# myRolloCtl_v2.net
KiCad netlist of a schematic drawn in EAGLE
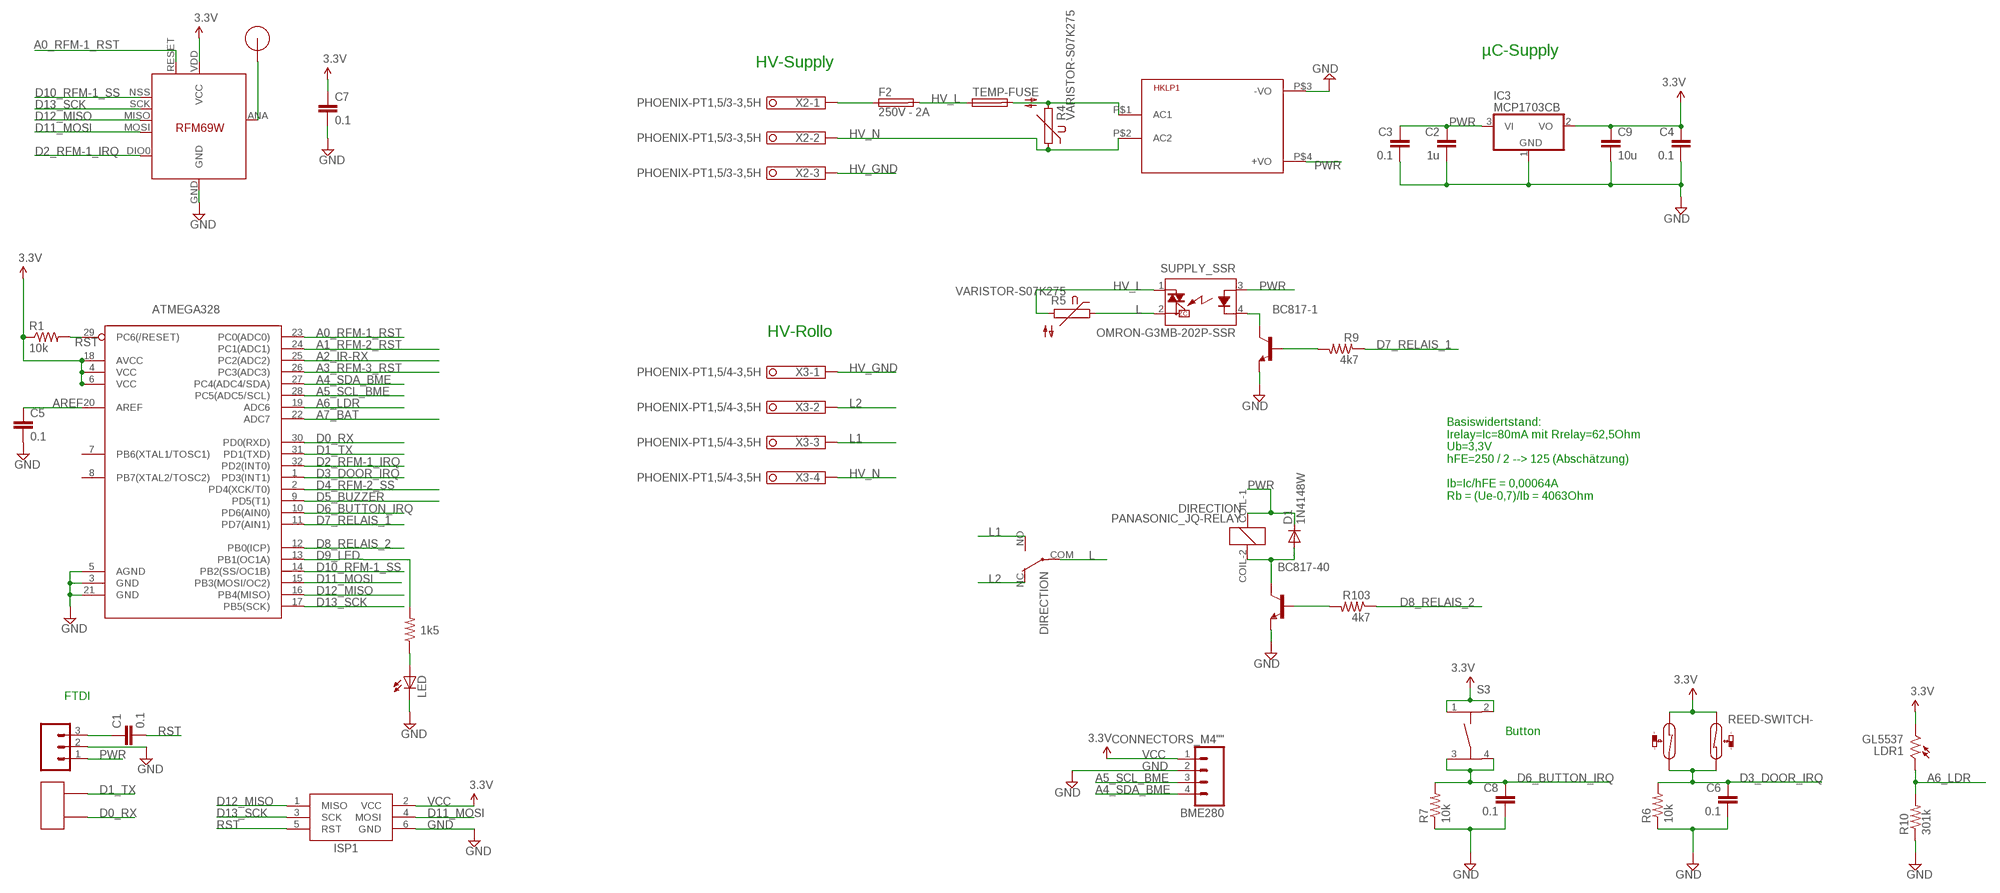
[diagram p0: schematic, sheet 1]

(export (version "E")
  (design (tool "Eeschema 10.0.6"))
  (components
    (comp (ref "ATMEGA328")
      (value "ATMega-328")
      (footprint "eagle-import:TQFP32-08")
      (libsource (lib "eagle-import") (part "ATMEGA168/328TQFP32"))
    )
    (comp (ref "BC817-1")
      (value "BC817-40-NPN-SOT23-BEC")
      (footprint "eagle-import:SOT23-BEC")
      (libsource (lib "eagle-import") (part "-NPN-SOT23-BECBC817-40"))
    )
    (comp (ref "BC817-40")
      (value "BC817-40-NPN-SOT23-BEC")
      (footprint "eagle-import:SOT23-BEC")
      (libsource (lib "eagle-import") (part "-NPN-SOT23-BECBC817-40"))
    )
    (comp (ref "BME280")
      (value "CONNECTORS_M4\"\"")
      (footprint "eagle-import:CONNECTORS_1X4")
      (libsource (lib "eagle-import") (part "CONNECTORS_M4{dblquote}{dblquote}"))
    )
    (comp (ref "C1")
      (value "0.1")
      (footprint "eagle-import:0603-CAP")
      (libsource (lib "eagle-import") (part "CAP0603-CAP"))
    )
    (comp (ref "C2")
      (value "1u")
      (footprint "eagle-import:0603-CAP")
      (libsource (lib "eagle-import") (part "CAP0603-CAP"))
    )
    (comp (ref "C3")
      (value "0.1")
      (footprint "eagle-import:0603-CAP")
      (libsource (lib "eagle-import") (part "CAP0603-CAP"))
    )
    (comp (ref "C4")
      (value "0.1")
      (footprint "eagle-import:0603-CAP")
      (libsource (lib "eagle-import") (part "CAP0603-CAP"))
    )
    (comp (ref "C5")
      (value "0.1")
      (footprint "eagle-import:0603-CAP")
      (libsource (lib "eagle-import") (part "CAP0603-CAP"))
    )
    (comp (ref "C6")
      (value "0.1")
      (footprint "eagle-import:0603-CAP")
      (libsource (lib "eagle-import") (part "CAP0603-CAP"))
    )
    (comp (ref "C7")
      (value "0.1")
      (footprint "eagle-import:0603-CAP")
      (libsource (lib "eagle-import") (part "CAP0603-CAP"))
    )
    (comp (ref "C8")
      (value "0.1")
      (footprint "eagle-import:0603-CAP")
      (libsource (lib "eagle-import") (part "CAP0603-CAP"))
    )
    (comp (ref "C9")
      (value "10u")
      (footprint "eagle-import:0805-CAP")
      (libsource (lib "eagle-import") (part "myLib_CAP0805-CAP"))
    )
    (comp (ref "D1")
      (value "1N4148W")
      (footprint "eagle-import:SOD123")
      (libsource (lib "eagle-import") (part "DIODE-SOD123"))
    )
    (comp (ref "DIRECTION")
      (value "PANASONIC_JQ-RELAY")
      (footprint "eagle-import:JQ1")
      (libsource (lib "eagle-import") (part "PANASONIC_JQ-RELAY"))
    )
    (comp (ref "F2")
      (value "250V - 2A")
      (footprint "eagle-import:TE5")
      (libsource (lib "eagle-import") (part "TE5"))
    )
    (comp (ref "HKLP1")
      (value "HKLPM01")
      (footprint "eagle-import:HKLPM01")
      (libsource (lib "eagle-import") (part "HKLPM01"))
    )
    (comp (ref "IC3")
      (value "MCP1703CB")
      (footprint "eagle-import:SOT23")
      (libsource (lib "eagle-import") (part "MCP1703CB"))
    )
    (comp (ref "ISP1")
      (value "AVRISP")
      (footprint "eagle-import:AVRISP-EDGE")
      (libsource (lib "eagle-import") (part "AVRISP"))
    )
    (comp (ref "JP2")
      (value "CONNECTORS_M3")
      (footprint "eagle-import:CONNECTORS_1X3")
      (libsource (lib "eagle-import") (part "CONNECTORS_M3"))
    )
    (comp (ref "LDR1")
      (value "GL5537")
      (footprint "eagle-import:M9960")
      (libsource (lib "eagle-import") (part "M9960_11A"))
    )
    (comp (ref "LED")
      (value "LED3MM")
      (footprint "eagle-import:LED3MM")
      (libsource (lib "eagle-import") (part "LED3MM"))
    )
    (comp (ref "R1")
      (value "10k")
      (footprint "eagle-import:0603-RES")
      (libsource (lib "eagle-import") (part "RESISTOR0603-RES"))
    )
    (comp (ref "R2")
      (value "1k5")
      (footprint "eagle-import:0603-RES")
      (libsource (lib "eagle-import") (part "RESISTOR0603-RES"))
    )
    (comp (ref "R4")
      (value "VARISTOR-S07K275")
      (footprint "eagle-import:S07K275")
      (libsource (lib "eagle-import") (part "VARISTOR-S07K275"))
    )
    (comp (ref "R5")
      (value "VARISTOR-S07K275")
      (footprint "eagle-import:S07K275")
      (libsource (lib "eagle-import") (part "VARISTOR-S07K275"))
    )
    (comp (ref "R6")
      (value "10k")
      (footprint "eagle-import:0603-RES")
      (libsource (lib "eagle-import") (part "RESISTOR0603-RES"))
    )
    (comp (ref "R7")
      (value "10k")
      (footprint "eagle-import:0603-RES")
      (libsource (lib "eagle-import") (part "RESISTOR0603-RES"))
    )
    (comp (ref "R9")
      (value "4k7")
      (footprint "eagle-import:0603-RES")
      (libsource (lib "eagle-import") (part "RESISTOR0603-RES"))
    )
    (comp (ref "R10")
      (value "301k")
      (footprint "eagle-import:0603-RES")
      (libsource (lib "eagle-import") (part "RESISTOR0603-RES"))
    )
    (comp (ref "R103")
      (value "4k7")
      (footprint "eagle-import:0603-RES")
      (libsource (lib "eagle-import") (part "RESISTOR0603-RES"))
    )
    (comp (ref "S1")
      (value "REED-SWITCH-")
      (footprint "eagle-import:REED_15X2MM")
      (libsource (lib "eagle-import") (part "REED-SWITCH-"))
    )
    (comp (ref "S2")
      (value "REED-SWITCH-")
      (footprint "eagle-import:REED_15X2MM")
      (libsource (lib "eagle-import") (part "REED-SWITCH-"))
    )
    (comp (ref "S3")
      (value "TASTER_SMD")
      (footprint "eagle-import:TASTER-1254_SMD")
      (libsource (lib "eagle-import") (part "TASTER_SMD"))
    )
    (comp (ref "SUPPLY_SSR")
      (value "OMRON-G3MB-202P-SSR")
      (footprint "eagle-import:OMRON-G3MB-202P-SSR")
      (libsource (lib "eagle-import") (part "OMRON-G3MB-202P-SSR"))
    )
    (comp (ref "TEMP-FUSE")
      (value "FUSESW-102T")
      (footprint "eagle-import:TEMP-FUSE")
      (libsource (lib "eagle-import") (part "FUSESW-102T"))
    )
    (comp (ref "U$1")
      (value "RFM12B_ANTENNA")
      (footprint "eagle-import:RFM12B-ANTENNA")
      (libsource (lib "eagle-import") (part "RFM12B_ANTENNA"))
    )
    (comp (ref "U$2")
      (value "HDR_2PIN")
      (footprint "eagle-import:1X02_NS")
      (libsource (lib "eagle-import") (part "HDR_2PIN"))
    )
    (comp (ref "U$5")
      (value "RFM69_MINIPADS")
      (footprint "eagle-import:RFM69W-MINPADS")
      (libsource (lib "eagle-import") (part "RFM69_MINIPADS"))
    )
    (comp (ref "X2")
      (value "PHOENIX-PT1,5/3-3,5H")
      (footprint "eagle-import:1984620")
      (libsource (lib "eagle-import") (part "PHOENIX-PT1,5/3-3,5H"))
    )
    (comp (ref "X3")
      (value "PHOENIX-PT1,5/4-3,5H")
      (footprint "eagle-import:1984633")
      (libsource (lib "eagle-import") (part "PHOENIX-PT1,5/4-3,5H"))
    )
  )
  (nets
    (net (code "1") (name "/A0_RFM-1_RST") (class "Default")
      (node (ref "ATMEGA328") (pin "23") (pinfunction "PC0(ADC0)_23") (pintype "bidirectional"))
      (node (ref "U$5") (pin "RESET") (pinfunction "RESET_RESET") (pintype "input"))
    )
    (net (code "2") (name "/A1_RFM-2_RST") (class "Default")
      (node (ref "ATMEGA328") (pin "24") (pinfunction "PC1(ADC1)_24") (pintype "bidirectional"))
    )
    (net (code "3") (name "/A2_IR-RX") (class "Default")
      (node (ref "ATMEGA328") (pin "25") (pinfunction "PC2(ADC2)_25") (pintype "bidirectional"))
    )
    (net (code "4") (name "/A3_RFM-3_RST") (class "Default")
      (node (ref "ATMEGA328") (pin "26") (pinfunction "PC3(ADC3)_26") (pintype "bidirectional"))
    )
    (net (code "5") (name "/A4_SDA_BME") (class "Default")
      (node (ref "ATMEGA328") (pin "27") (pinfunction "PC4(ADC4/SDA)_27") (pintype "bidirectional"))
      (node (ref "BME280") (pin "4") (pinfunction "4_4") (pintype "passive"))
    )
    (net (code "6") (name "/A5_SCL_BME") (class "Default")
      (node (ref "ATMEGA328") (pin "28") (pinfunction "PC5(ADC5/SCL)_28") (pintype "bidirectional"))
      (node (ref "BME280") (pin "3") (pinfunction "3_3") (pintype "passive"))
    )
    (net (code "7") (name "/A6_LDR") (class "Default")
      (node (ref "ATMEGA328") (pin "19") (pinfunction "ADC6_19") (pintype "bidirectional"))
      (node (ref "LDR1") (pin "1") (pinfunction "1_1") (pintype "passive"))
      (node (ref "R10") (pin "2") (pinfunction "2_2") (pintype "passive"))
    )
    (net (code "8") (name "/A7_BAT") (class "Default")
      (node (ref "ATMEGA328") (pin "22") (pinfunction "ADC7_22") (pintype "bidirectional"))
    )
    (net (code "9") (name "/AREF") (class "Default")
      (node (ref "ATMEGA328") (pin "20") (pinfunction "AREF_20") (pintype "bidirectional"))
      (node (ref "C5") (pin "1") (pinfunction "1_1") (pintype "passive"))
    )
    (net (code "10") (name "/D0_RX") (class "Default")
      (node (ref "ATMEGA328") (pin "30") (pinfunction "PD0(RXD)_30") (pintype "bidirectional"))
      (node (ref "U$2") (pin "1") (pinfunction "P$1_1") (pintype "bidirectional"))
    )
    (net (code "11") (name "/D1_TX") (class "Default")
      (node (ref "ATMEGA328") (pin "31") (pinfunction "PD1(TXD)_31") (pintype "bidirectional"))
      (node (ref "U$2") (pin "2") (pinfunction "P$2_2") (pintype "bidirectional"))
    )
    (net (code "12") (name "/D2_RFM-1_IRQ") (class "Default")
      (node (ref "ATMEGA328") (pin "32") (pinfunction "PD2(INT0)_32") (pintype "bidirectional"))
      (node (ref "U$5") (pin "DIO0") (pinfunction "DIO0/IRQ_DIO0") (pintype "open_collector"))
    )
    (net (code "13") (name "/D3_DOOR_IRQ") (class "Default")
      (node (ref "ATMEGA328") (pin "1") (pinfunction "PD3(INT1)_1") (pintype "bidirectional"))
      (node (ref "C6") (pin "1") (pinfunction "1_1") (pintype "passive"))
      (node (ref "R6") (pin "2") (pinfunction "2_2") (pintype "passive"))
      (node (ref "S1") (pin "2") (pinfunction "2_2") (pintype "passive"))
      (node (ref "S2") (pin "1") (pinfunction "1_1") (pintype "passive"))
    )
    (net (code "14") (name "/D4_RFM-2_SS") (class "Default")
      (node (ref "ATMEGA328") (pin "2") (pinfunction "PD4(XCK/T0)_2") (pintype "bidirectional"))
    )
    (net (code "15") (name "/D5_BUZZER") (class "Default")
      (node (ref "ATMEGA328") (pin "9") (pinfunction "PD5(T1)_9") (pintype "bidirectional"))
    )
    (net (code "16") (name "/D6_BUTTON_IRQ") (class "Default")
      (node (ref "ATMEGA328") (pin "10") (pinfunction "PD6(AIN0)_10") (pintype "bidirectional"))
      (node (ref "C8") (pin "1") (pinfunction "1_1") (pintype "passive"))
      (node (ref "R7") (pin "2") (pinfunction "2_2") (pintype "passive"))
      (node (ref "S3") (pin "3") (pinfunction "3_3") (pintype "passive"))
      (node (ref "S3") (pin "4") (pinfunction "4_4") (pintype "passive"))
    )
    (net (code "17") (name "/D7_RELAIS_1") (class "Default")
      (node (ref "ATMEGA328") (pin "11") (pinfunction "PD7(AIN1)_11") (pintype "bidirectional"))
      (node (ref "R9") (pin "1") (pinfunction "1_1") (pintype "passive"))
    )
    (net (code "18") (name "/D8_RELAIS_2") (class "Default")
      (node (ref "ATMEGA328") (pin "12") (pinfunction "PB0(ICP)_12") (pintype "bidirectional"))
      (node (ref "R103") (pin "1") (pinfunction "1_1") (pintype "passive"))
    )
    (net (code "19") (name "/D9_LED") (class "Default")
      (node (ref "ATMEGA328") (pin "13") (pinfunction "PB1(OC1A)_13") (pintype "bidirectional"))
      (node (ref "R2") (pin "2") (pinfunction "2_2") (pintype "passive"))
    )
    (net (code "20") (name "/D10_RFM-1_SS") (class "Default")
      (node (ref "ATMEGA328") (pin "14") (pinfunction "PB2(SS/OC1B)_14") (pintype "bidirectional"))
      (node (ref "U$5") (pin "NSS") (pinfunction "SEL_NSS") (pintype "input"))
    )
    (net (code "21") (name "/D11_MOSI") (class "Default")
      (node (ref "ATMEGA328") (pin "15") (pinfunction "PB3(MOSI/OC2)_15") (pintype "bidirectional"))
      (node (ref "ISP1") (pin "4") (pinfunction "MOSI_4") (pintype "output"))
      (node (ref "U$5") (pin "MOSI") (pinfunction "MOSI_MOSI") (pintype "output"))
    )
    (net (code "22") (name "/D12_MISO") (class "Default")
      (node (ref "ATMEGA328") (pin "16") (pinfunction "PB4(MISO)_16") (pintype "bidirectional"))
      (node (ref "ISP1") (pin "1") (pinfunction "MISO_1") (pintype "input"))
      (node (ref "U$5") (pin "MISO") (pinfunction "MISO_MISO") (pintype "input"))
    )
    (net (code "23") (name "/D13_SCK") (class "Default")
      (node (ref "ATMEGA328") (pin "17") (pinfunction "PB5(SCK)_17") (pintype "bidirectional"))
      (node (ref "ISP1") (pin "3") (pinfunction "SCK_3") (pintype "output"))
      (node (ref "U$5") (pin "SCK") (pinfunction "SCK_SCK") (pintype "input"))
    )
    (net (code "24") (name "/HV_GND") (class "Default")
      (node (ref "X2") (pin "3") (pinfunction "K_3") (pintype "passive"))
      (node (ref "X3") (pin "1") (pinfunction "K_1") (pintype "passive"))
    )
    (net (code "25") (name "/HV_L") (class "Default")
      (node (ref "F2") (pin "2") (pinfunction "2_2") (pintype "passive"))
      (node (ref "R5") (pin "2") (pinfunction "2_2") (pintype "passive"))
      (node (ref "SUPPLY_SSR") (pin "1") (pinfunction "DS1_1") (pintype "passive"))
      (node (ref "TEMP-FUSE") (pin "1") (pinfunction "1_1") (pintype "passive"))
    )
    (net (code "26") (name "/HV_N") (class "Default")
      (node (ref "HKLP1") (pin "P$2") (pinfunction "AC2_P$2") (pintype "bidirectional"))
      (node (ref "R4") (pin "1") (pinfunction "1_1") (pintype "passive"))
      (node (ref "X2") (pin "2") (pinfunction "K_2") (pintype "passive"))
      (node (ref "X3") (pin "4") (pinfunction "K_4") (pintype "passive"))
    )
    (net (code "27") (name "/L") (class "Default")
      (node (ref "DIRECTION") (pin "COM") (pinfunction "P_COM") (pintype "passive"))
      (node (ref "R5") (pin "1") (pinfunction "1_1") (pintype "passive"))
      (node (ref "SUPPLY_SSR") (pin "2") (pinfunction "DS2_2") (pintype "passive"))
    )
    (net (code "28") (name "/L1") (class "Default")
      (node (ref "DIRECTION") (pin "NO") (pinfunction "S_NO") (pintype "passive"))
      (node (ref "X3") (pin "3") (pinfunction "K_3") (pintype "passive"))
    )
    (net (code "29") (name "/L2") (class "Default")
      (node (ref "DIRECTION") (pin "NC") (pinfunction "O_NC") (pintype "passive"))
      (node (ref "X3") (pin "2") (pinfunction "K_2") (pintype "passive"))
    )
    (net (code "30") (name "/PWR") (class "Default")
      (node (ref "C2") (pin "1") (pinfunction "1_1") (pintype "passive"))
      (node (ref "C3") (pin "1") (pinfunction "1_1") (pintype "passive"))
      (node (ref "D1") (pin "C") (pinfunction "C_C") (pintype "passive"))
      (node (ref "DIRECTION") (pin "COIL-1") (pinfunction "1_COIL-1") (pintype "passive"))
      (node (ref "HKLP1") (pin "P$4") (pinfunction "+VO_P$4") (pintype "bidirectional"))
      (node (ref "IC3") (pin "3") (pinfunction "VI_3") (pintype "input"))
      (node (ref "JP2") (pin "1") (pinfunction "1_1") (pintype "passive"))
      (node (ref "SUPPLY_SSR") (pin "3") (pinfunction "A_3") (pintype "passive"))
    )
    (net (code "31") (name "/RST") (class "Default")
      (node (ref "ATMEGA328") (pin "29") (pinfunction "PC6(/RESET)_29") (pintype "bidirectional"))
      (node (ref "C1") (pin "2") (pinfunction "2_2") (pintype "passive"))
      (node (ref "ISP1") (pin "5") (pinfunction "RST_5") (pintype "output"))
      (node (ref "R1") (pin "2") (pinfunction "2_2") (pintype "passive"))
    )
    (net (code "32") (name "3.3V") (class "Default")
      (node (ref "ATMEGA328") (pin "18") (pinfunction "AVCC_18") (pintype "bidirectional"))
      (node (ref "ATMEGA328") (pin "4") (pinfunction "VCC_4") (pintype "bidirectional"))
      (node (ref "ATMEGA328") (pin "6") (pinfunction "VCC_6") (pintype "bidirectional"))
      (node (ref "BME280") (pin "1") (pinfunction "1_1") (pintype "passive"))
      (node (ref "C4") (pin "1") (pinfunction "1_1") (pintype "passive"))
      (node (ref "C7") (pin "1") (pinfunction "1_1") (pintype "passive"))
      (node (ref "C9") (pin "1") (pinfunction "1_1") (pintype "passive"))
      (node (ref "IC3") (pin "2") (pinfunction "VO_2") (pintype "passive"))
      (node (ref "ISP1") (pin "2") (pinfunction "VCC_2") (pintype "power_in"))
      (node (ref "LDR1") (pin "2") (pinfunction "2_2") (pintype "passive"))
      (node (ref "R1") (pin "1") (pinfunction "1_1") (pintype "passive"))
      (node (ref "S1") (pin "1") (pinfunction "1_1") (pintype "passive"))
      (node (ref "S2") (pin "2") (pinfunction "2_2") (pintype "passive"))
      (node (ref "S3") (pin "1") (pinfunction "1_1") (pintype "passive"))
      (node (ref "S3") (pin "2") (pinfunction "2_2") (pintype "passive"))
      (node (ref "U$5") (pin "VDD") (pinfunction "VCC_VDD") (pintype "power_in"))
    )
    (net (code "33") (name "GND") (class "Default")
      (node (ref "ATMEGA328") (pin "21") (pinfunction "GND_21") (pintype "bidirectional"))
      (node (ref "ATMEGA328") (pin "3") (pinfunction "GND_3") (pintype "bidirectional"))
      (node (ref "ATMEGA328") (pin "5") (pinfunction "AGND_5") (pintype "bidirectional"))
      (node (ref "BC817-1") (pin "E") (pinfunction "E_E") (pintype "passive"))
      (node (ref "BC817-40") (pin "E") (pinfunction "E_E") (pintype "passive"))
      (node (ref "BME280") (pin "2") (pinfunction "2_2") (pintype "passive"))
      (node (ref "C2") (pin "2") (pinfunction "2_2") (pintype "passive"))
      (node (ref "C3") (pin "2") (pinfunction "2_2") (pintype "passive"))
      (node (ref "C4") (pin "2") (pinfunction "2_2") (pintype "passive"))
      (node (ref "C5") (pin "2") (pinfunction "2_2") (pintype "passive"))
      (node (ref "C6") (pin "2") (pinfunction "2_2") (pintype "passive"))
      (node (ref "C7") (pin "2") (pinfunction "2_2") (pintype "passive"))
      (node (ref "C8") (pin "2") (pinfunction "2_2") (pintype "passive"))
      (node (ref "C9") (pin "2") (pinfunction "2_2") (pintype "passive"))
      (node (ref "HKLP1") (pin "P$3") (pinfunction "-VO_P$3") (pintype "bidirectional"))
      (node (ref "IC3") (pin "1") (pinfunction "GND_1") (pintype "passive"))
      (node (ref "ISP1") (pin "6") (pinfunction "GND_6") (pintype "power_in"))
      (node (ref "JP2") (pin "2") (pinfunction "2_2") (pintype "passive"))
      (node (ref "LED") (pin "K") (pinfunction "C_K") (pintype "passive"))
      (node (ref "R10") (pin "1") (pinfunction "1_1") (pintype "passive"))
      (node (ref "R6") (pin "1") (pinfunction "1_1") (pintype "passive"))
      (node (ref "R7") (pin "1") (pinfunction "1_1") (pintype "passive"))
      (node (ref "U$5") (pin "GND") (pinfunction "GND_GND") (pintype "power_in"))
    )
    (net (code "34") (name "Net-(BC817-1-PadB)") (class "Default")
      (node (ref "BC817-1") (pin "B") (pinfunction "B_B") (pintype "passive"))
      (node (ref "R9") (pin "2") (pinfunction "2_2") (pintype "passive"))
    )
    (net (code "35") (name "Net-(BC817-40-PadB)") (class "Default")
      (node (ref "BC817-40") (pin "B") (pinfunction "B_B") (pintype "passive"))
      (node (ref "R103") (pin "2") (pinfunction "2_2") (pintype "passive"))
    )
    (net (code "36") (name "Net-(C1-Pad1)") (class "Default")
      (node (ref "C1") (pin "1") (pinfunction "1_1") (pintype "passive"))
      (node (ref "JP2") (pin "3") (pinfunction "3_3") (pintype "passive"))
    )
    (net (code "37") (name "Net-(DIRECTIONB-2)") (class "Default")
      (node (ref "BC817-40") (pin "C") (pinfunction "C_C") (pintype "passive"))
      (node (ref "D1") (pin "A") (pinfunction "A_A") (pintype "passive"))
      (node (ref "DIRECTION") (pin "COIL-2") (pinfunction "2_COIL-2") (pintype "passive"))
    )
    (net (code "38") (name "Net-(HKLP1-AC1)") (class "Default")
      (node (ref "HKLP1") (pin "P$1") (pinfunction "AC1_P$1") (pintype "bidirectional"))
      (node (ref "R4") (pin "2") (pinfunction "2_2") (pintype "passive"))
      (node (ref "TEMP-FUSE") (pin "2") (pinfunction "2_2") (pintype "passive"))
    )
    (net (code "39") (name "Net-(LED-PadA)") (class "Default")
      (node (ref "LED") (pin "A") (pinfunction "A_A") (pintype "passive"))
      (node (ref "R2") (pin "1") (pinfunction "1_1") (pintype "passive"))
    )
    (net (code "40") (name "Net-(SUPPLY_SSR-K)") (class "Default")
      (node (ref "BC817-1") (pin "C") (pinfunction "C_C") (pintype "passive"))
      (node (ref "SUPPLY_SSR") (pin "4") (pinfunction "K_4") (pintype "passive"))
    )
    (net (code "41") (name "Net-(U$1-1)") (class "Default")
      (node (ref "U$1") (pin "P$1") (pinfunction "1_P$1") (pintype "bidirectional"))
      (node (ref "U$5") (pin "ANA") (pinfunction "ANT_ANA") (pintype "passive"))
    )
    (net (code "42") (name "Net-(X2A-K)") (class "Default")
      (node (ref "F2") (pin "1") (pinfunction "1_1") (pintype "passive"))
      (node (ref "X2") (pin "1") (pinfunction "K_1") (pintype "passive"))
    )
    (net (code "43") (name "unconnected-(ATMEGA328-PB6(XTAL1{slash}TOSC1)-Pad7)") (class "Default")
      (node (ref "ATMEGA328") (pin "7") (pinfunction "PB6(XTAL1/TOSC1)_7") (pintype "bidirectional"))
    )
    (net (code "44") (name "unconnected-(ATMEGA328-PB7(XTAL2{slash}TOSC2)-Pad8)") (class "Default")
      (node (ref "ATMEGA328") (pin "8") (pinfunction "PB7(XTAL2/TOSC2)_8") (pintype "bidirectional"))
    )
  )
)
